# strain-gauge-amplifier-v2.net
KiCad netlist of a schematic drawn in EAGLE
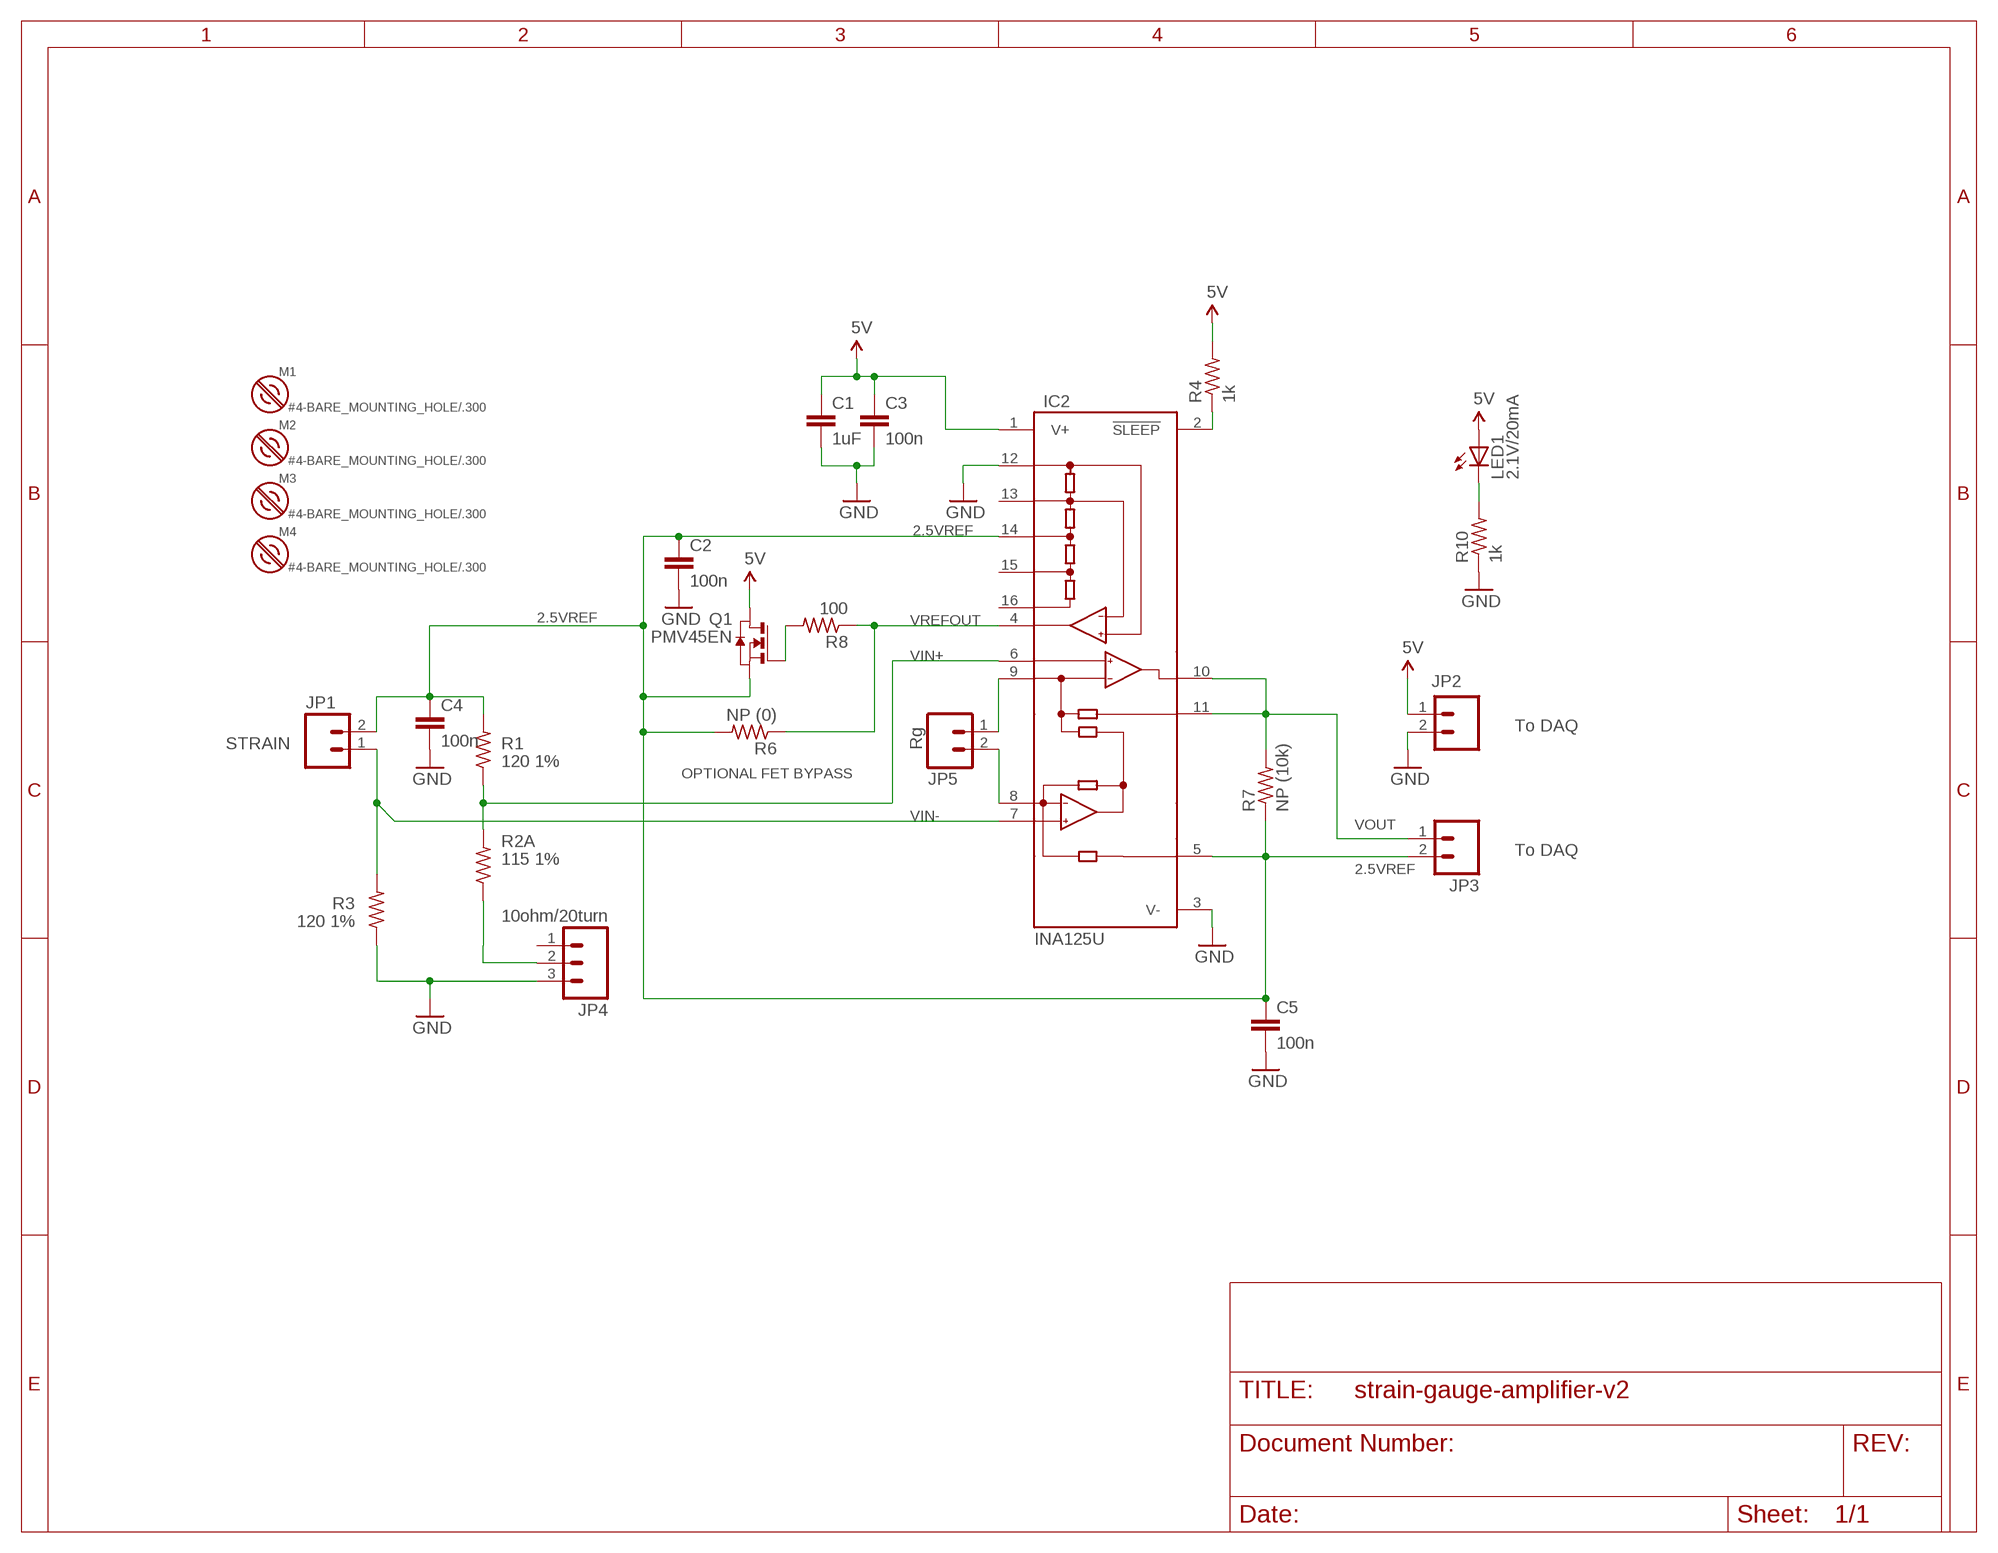
[diagram p0: schematic, sheet 1]

(export (version "E")
  (design (tool "Eeschema 10.0.6"))
  (components
    (comp (ref "C1")
      (value "1uF")
      (footprint "eagle-import:0805-C-NOSILK")
      (libsource (lib "eagle-import") (part "C-EU0805-C-NOSILK"))
    )
    (comp (ref "C2")
      (value "100n")
      (footprint "eagle-import:0805-C-NOSILK")
      (libsource (lib "eagle-import") (part "C-EU0805-C-NOSILK"))
    )
    (comp (ref "C3")
      (value "100n")
      (footprint "eagle-import:0805-C-NOSILK")
      (libsource (lib "eagle-import") (part "C-EU0805-C-NOSILK"))
    )
    (comp (ref "C4")
      (value "100n")
      (footprint "eagle-import:0805-C-NOSILK")
      (libsource (lib "eagle-import") (part "C-EU0805-C-NOSILK"))
    )
    (comp (ref "C5")
      (value "100n")
      (footprint "eagle-import:0805-C-NOSILK")
      (libsource (lib "eagle-import") (part "C-EU0805-C-NOSILK"))
    )
    (comp (ref "IC2")
      (value "INA125U")
      (footprint "eagle-import:SO16-1")
      (fields (field (name "MF") "TEXAS INSTRUMENT CONNECTORS"))
      (libsource (lib "eagle-import") (part "INA125U"))
    )
    (comp (ref "JP1")
      (value "STRAIN")
      (footprint "eagle-import:SCREWTERMINAL-5MM-2")
      (libsource (lib "eagle-import") (part "M025MM"))
    )
    (comp (ref "JP2")
      (value "M025MM")
      (footprint "eagle-import:SCREWTERMINAL-5MM-2")
      (libsource (lib "eagle-import") (part "M025MM"))
    )
    (comp (ref "JP3")
      (value "M025MM")
      (footprint "eagle-import:SCREWTERMINAL-5MM-2")
      (libsource (lib "eagle-import") (part "M025MM"))
    )
    (comp (ref "JP4")
      (value "10ohm/20turn")
      (footprint "eagle-import:1X03_NO_SILK")
      (libsource (lib "eagle-import") (part "M031X03_NO_SILK"))
    )
    (comp (ref "JP5")
      (value "Rg")
      (footprint "eagle-import:SCREWTERMINAL-5MM-2")
      (libsource (lib "eagle-import") (part "M025MM"))
    )
    (comp (ref "LED1")
      (value "2.1V/20mA")
      (footprint "eagle-import:LED-0603")
      (libsource (lib "eagle-import") (part "LED0603"))
    )
    (comp (ref "M1")
      (value "#4-BARE_MOUNTING_HOLE/.300")
      (footprint "eagle-import:#4_.300-BARE+STD_NUT_OR_STAR_WASHER")
      (libsource (lib "eagle-import") (part "#4-BARE_MOUNTING_HOLE/.300"))
    )
    (comp (ref "M2")
      (value "#4-BARE_MOUNTING_HOLE/.300")
      (footprint "eagle-import:#4_.300-BARE+STD_NUT_OR_STAR_WASHER")
      (libsource (lib "eagle-import") (part "#4-BARE_MOUNTING_HOLE/.300"))
    )
    (comp (ref "M3")
      (value "#4-BARE_MOUNTING_HOLE/.300")
      (footprint "eagle-import:#4_.300-BARE+STD_NUT_OR_STAR_WASHER")
      (libsource (lib "eagle-import") (part "#4-BARE_MOUNTING_HOLE/.300"))
    )
    (comp (ref "M4")
      (value "#4-BARE_MOUNTING_HOLE/.300")
      (footprint "eagle-import:#4_.300-BARE+STD_NUT_OR_STAR_WASHER")
      (libsource (lib "eagle-import") (part "#4-BARE_MOUNTING_HOLE/.300"))
    )
    (comp (ref "Q1")
      (value "PMV45EN")
      (footprint "eagle-import:SOT23")
      (libsource (lib "eagle-import") (part "PMV45EN"))
    )
    (comp (ref "R1")
      (value "120 1%")
      (footprint "eagle-import:0805-C-NOSILK")
      (libsource (lib "eagle-import") (part "R-US_0805-C-NOSILK"))
    )
    (comp (ref "R2A")
      (value "115 1%")
      (footprint "eagle-import:0805-C-NOSILK")
      (libsource (lib "eagle-import") (part "R-US_0805-C-NOSILK"))
    )
    (comp (ref "R3")
      (value "120 1%")
      (footprint "eagle-import:0805-C-NOSILK")
      (libsource (lib "eagle-import") (part "R-US_0805-C-NOSILK"))
    )
    (comp (ref "R4")
      (value "1k")
      (footprint "eagle-import:0805-C-NOSILK")
      (libsource (lib "eagle-import") (part "R-US_0805-C-NOSILK"))
    )
    (comp (ref "R6")
      (value "NP (0)")
      (footprint "eagle-import:0805-C-NOSILK")
      (libsource (lib "eagle-import") (part "R-US_0805-C-NOSILK"))
    )
    (comp (ref "R7")
      (value "NP (10k)")
      (footprint "eagle-import:0805-C-NOSILK")
      (libsource (lib "eagle-import") (part "R-US_0805-C-NOSILK"))
    )
    (comp (ref "R8")
      (value "100")
      (footprint "eagle-import:0805-C-NOSILK")
      (libsource (lib "eagle-import") (part "R-US_0805-C-NOSILK"))
    )
    (comp (ref "R10")
      (value "1k")
      (footprint "eagle-import:0805-C-NOSILK")
      (libsource (lib "eagle-import") (part "R-US_0805-C-NOSILK"))
    )
  )
  (nets
    (net (code "1") (name "/2.5VREF") (class "Default")
      (node (ref "C2") (pin "1") (pinfunction "1_1") (pintype "passive"))
      (node (ref "C4") (pin "1") (pinfunction "1_1") (pintype "passive"))
      (node (ref "C5") (pin "1") (pinfunction "1_1") (pintype "passive"))
      (node (ref "IC2") (pin "14") (pinfunction "REF2.5_14") (pintype "output"))
      (node (ref "IC2") (pin "5") (pinfunction "REF_5") (pintype "passive"))
      (node (ref "JP1") (pin "2") (pinfunction "2_2") (pintype "passive"))
      (node (ref "JP3") (pin "2") (pinfunction "2_2") (pintype "passive"))
      (node (ref "Q1") (pin "2") (pinfunction "S_2") (pintype "passive"))
      (node (ref "R1") (pin "2") (pinfunction "2_2") (pintype "passive"))
      (node (ref "R6") (pin "2") (pinfunction "2_2") (pintype "passive"))
      (node (ref "R7") (pin "1") (pinfunction "1_1") (pintype "passive"))
    )
    (net (code "2") (name "/VIN+") (class "Default")
      (node (ref "IC2") (pin "6") (pinfunction "+IN_6") (pintype "input"))
      (node (ref "R1") (pin "1") (pinfunction "1_1") (pintype "passive"))
      (node (ref "R2A") (pin "2") (pinfunction "2_2") (pintype "passive"))
    )
    (net (code "3") (name "/VIN-") (class "Default")
      (node (ref "IC2") (pin "7") (pinfunction "-VIN_7") (pintype "input"))
      (node (ref "JP1") (pin "1") (pinfunction "1_1") (pintype "passive"))
      (node (ref "R3") (pin "2") (pinfunction "2_2") (pintype "passive"))
    )
    (net (code "4") (name "/VOUT") (class "Default")
      (node (ref "IC2") (pin "10") (pinfunction "OUT_10") (pintype "output"))
      (node (ref "IC2") (pin "11") (pinfunction "SENSE_11") (pintype "passive"))
      (node (ref "JP3") (pin "1") (pinfunction "1_1") (pintype "passive"))
      (node (ref "R7") (pin "2") (pinfunction "2_2") (pintype "passive"))
    )
    (net (code "5") (name "/VREFOUT") (class "Default")
      (node (ref "IC2") (pin "4") (pinfunction "REFOUT_4") (pintype "output"))
      (node (ref "R6") (pin "1") (pinfunction "1_1") (pintype "passive"))
      (node (ref "R8") (pin "1") (pinfunction "1_1") (pintype "passive"))
    )
    (net (code "6") (name "5V") (class "Default")
      (node (ref "C1") (pin "1") (pinfunction "1_1") (pintype "passive"))
      (node (ref "C3") (pin "1") (pinfunction "1_1") (pintype "passive"))
      (node (ref "IC2") (pin "1") (pinfunction "V+_1") (pintype "power_in"))
      (node (ref "JP2") (pin "1") (pinfunction "1_1") (pintype "passive"))
      (node (ref "LED1") (pin "A") (pinfunction "A_A") (pintype "passive"))
      (node (ref "Q1") (pin "3") (pinfunction "D_3") (pintype "passive"))
      (node (ref "R4") (pin "2") (pinfunction "2_2") (pintype "passive"))
    )
    (net (code "7") (name "GND") (class "Default")
      (node (ref "C1") (pin "2") (pinfunction "2_2") (pintype "passive"))
      (node (ref "C2") (pin "2") (pinfunction "2_2") (pintype "passive"))
      (node (ref "C3") (pin "2") (pinfunction "2_2") (pintype "passive"))
      (node (ref "C4") (pin "2") (pinfunction "2_2") (pintype "passive"))
      (node (ref "C5") (pin "2") (pinfunction "2_2") (pintype "passive"))
      (node (ref "IC2") (pin "12") (pinfunction "REFCOM_12") (pintype "passive"))
      (node (ref "IC2") (pin "3") (pinfunction "V-_3") (pintype "power_in"))
      (node (ref "JP2") (pin "2") (pinfunction "2_2") (pintype "passive"))
      (node (ref "JP4") (pin "3") (pinfunction "3_3") (pintype "passive"))
      (node (ref "R10") (pin "1") (pinfunction "1_1") (pintype "passive"))
      (node (ref "R3") (pin "1") (pinfunction "1_1") (pintype "passive"))
    )
    (net (code "8") (name "Net-(IC2-RG-Pad8)") (class "Default")
      (node (ref "IC2") (pin "8") (pinfunction "RG_8") (pintype "passive"))
      (node (ref "JP5") (pin "2") (pinfunction "2_2") (pintype "passive"))
    )
    (net (code "9") (name "Net-(IC2-RG-Pad9)") (class "Default")
      (node (ref "IC2") (pin "9") (pinfunction "RG_9") (pintype "passive"))
      (node (ref "JP5") (pin "1") (pinfunction "1_1") (pintype "passive"))
    )
    (net (code "10") (name "Net-(IC2-~{SLEEP})") (class "Default")
      (node (ref "IC2") (pin "2") (pinfunction "~{SLEEP}_2") (pintype "input"))
      (node (ref "R4") (pin "1") (pinfunction "1_1") (pintype "passive"))
    )
    (net (code "11") (name "Net-(JP4-Pad2)") (class "Default")
      (node (ref "JP4") (pin "2") (pinfunction "2_2") (pintype "passive"))
      (node (ref "R2A") (pin "1") (pinfunction "1_1") (pintype "passive"))
    )
    (net (code "12") (name "Net-(LED1-PadC)") (class "Default")
      (node (ref "LED1") (pin "C") (pinfunction "C_C") (pintype "passive"))
      (node (ref "R10") (pin "2") (pinfunction "2_2") (pintype "passive"))
    )
    (net (code "13") (name "Net-(Q1-G)") (class "Default")
      (node (ref "Q1") (pin "1") (pinfunction "G_1") (pintype "passive"))
      (node (ref "R8") (pin "2") (pinfunction "2_2") (pintype "passive"))
    )
    (net (code "14") (name "unconnected-(IC2-REF5-Pad15)") (class "Default")
      (node (ref "IC2") (pin "15") (pinfunction "REF5_15") (pintype "output"))
    )
    (net (code "15") (name "unconnected-(IC2-REF10-Pad16)") (class "Default")
      (node (ref "IC2") (pin "16") (pinfunction "REF10_16") (pintype "output"))
    )
    (net (code "16") (name "unconnected-(IC2-REFBG-Pad13)") (class "Default")
      (node (ref "IC2") (pin "13") (pinfunction "REFBG_13") (pintype "output"))
    )
    (net (code "17") (name "unconnected-(JP4-Pad1)") (class "Default")
      (node (ref "JP4") (pin "1") (pinfunction "1_1") (pintype "passive"))
    )
  )
)
